# WCE_Programming.net
KiCad netlist of a schematic drawn in Altium Designer
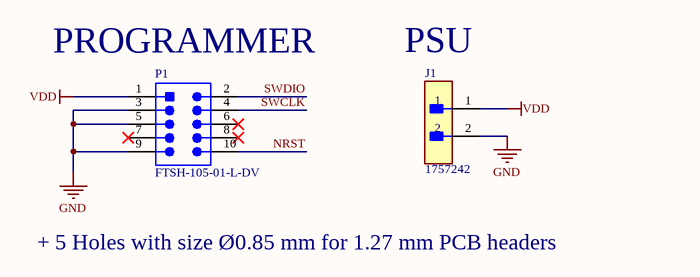
[diagram p0: WCE_Programming.SchDoc]

(export (version "E")
  (design (tool "Eeschema 10.0.6"))
  (components
    (comp (ref "J1")
      (value "1757242")
      (footprint "FP-1757242-MFG")
      (description "TERM BLOCK HDR 2POS 90DEG 5.08MM")
      (fields (field (name "VOLTAGE") "300V"))
      (libsource (lib "Altium Content Vault") (part "3bc925449376181038e59eaffc5286c"))
    )
    (comp (ref "P1")
      (value "FTSH-105-01-L-DV")
      (footprint "SMTC-FTSH-105-01-L-DV_V")
      (description "Male Header, Pitch 1.27 mm, 2 x 5 Position, Height 5.96 mm, -55 to 125 degC, RoHS, Bulk")
      (fields (field (name "MANUFACTURER") "Samtec"))
      (libsource (lib "Altium Content Vault") (part "CN-2P-M-R10"))
    )
  )
  (nets
    (net (code "1") (name "/NRST") (class "Default")
      (node (ref "P1") (pin "10") (pinfunction "10_10") (pintype "passive"))
    )
    (net (code "2") (name "/SWCLK") (class "Default")
      (node (ref "P1") (pin "4") (pinfunction "4_4") (pintype "passive"))
    )
    (net (code "3") (name "/SWDIO") (class "Default")
      (node (ref "P1") (pin "2") (pinfunction "2_2") (pintype "passive"))
    )
    (net (code "4") (name "GND") (class "Default")
      (node (ref "J1") (pin "2") (pinfunction "2_2") (pintype "passive"))
      (node (ref "P1") (pin "3") (pinfunction "3_3") (pintype "passive"))
      (node (ref "P1") (pin "5") (pinfunction "5_5") (pintype "passive"))
      (node (ref "P1") (pin "9") (pinfunction "9_9") (pintype "passive"))
    )
    (net (code "5") (name "VDD") (class "Default")
      (node (ref "J1") (pin "1") (pinfunction "1_1") (pintype "passive"))
      (node (ref "P1") (pin "1") (pinfunction "1_1") (pintype "passive"))
    )
    (net (code "6") (name "unconnected-(P1-Pad6)") (class "Default")
      (node (ref "P1") (pin "6") (pinfunction "6_6") (pintype "passive+no_connect"))
    )
    (net (code "7") (name "unconnected-(P1-Pad7)") (class "Default")
      (node (ref "P1") (pin "7") (pinfunction "7_7") (pintype "passive+no_connect"))
    )
    (net (code "8") (name "unconnected-(P1-Pad8)") (class "Default")
      (node (ref "P1") (pin "8") (pinfunction "8_8") (pintype "passive+no_connect"))
    )
  )
)
